# New_Project_ufcd_6024_2.net
KiCad netlist of a schematic drawn in EasyEDA Pro
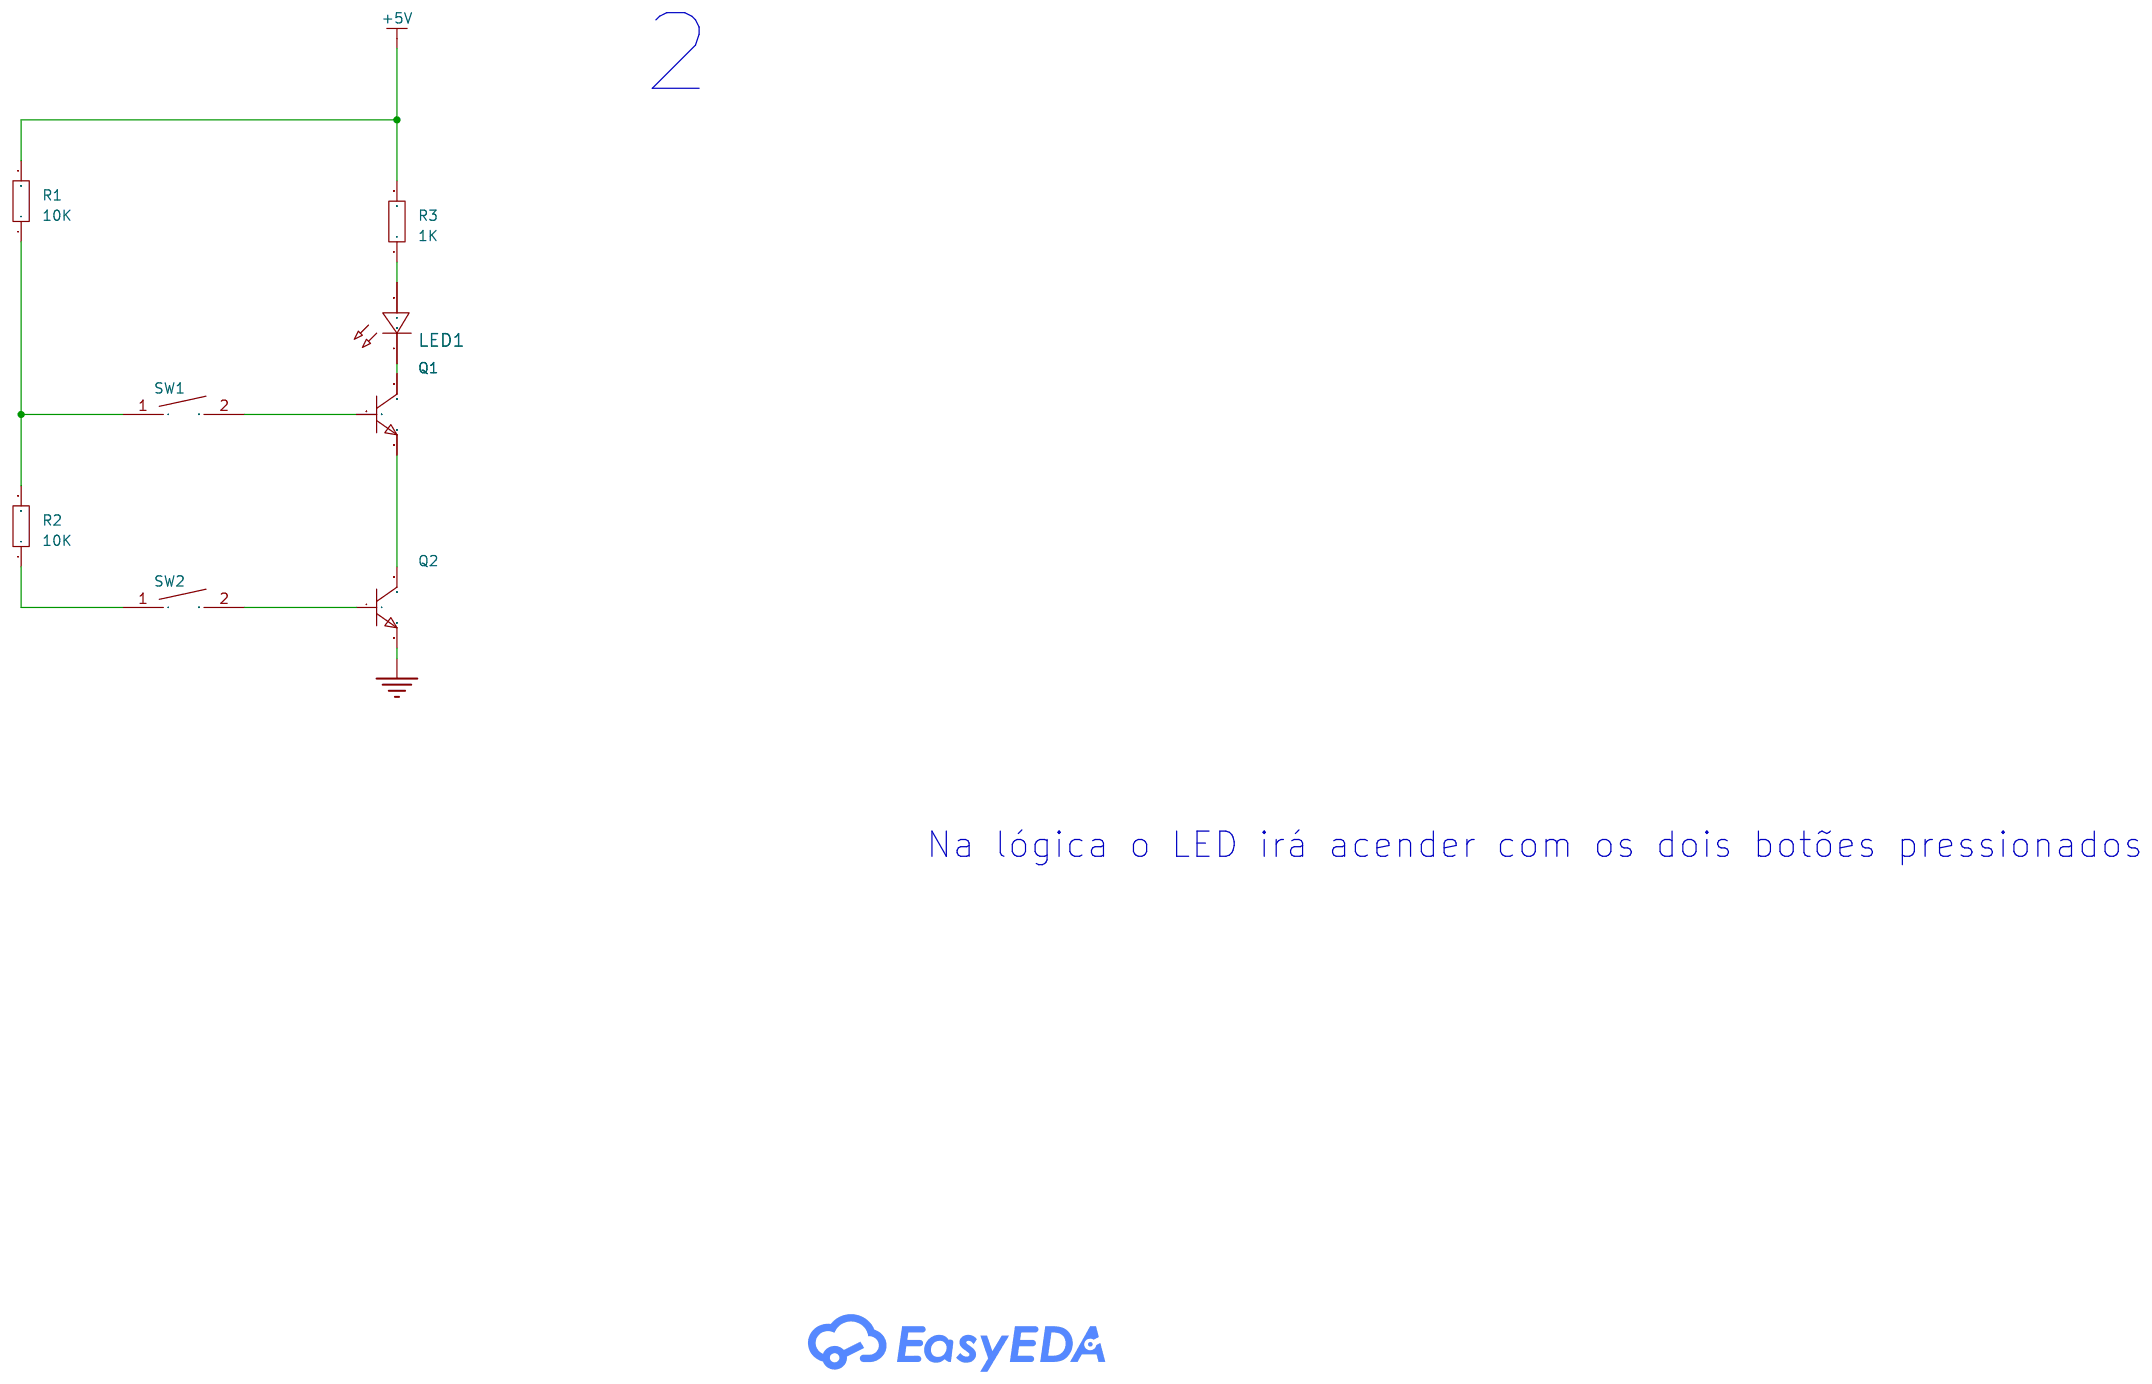
[diagram p0: schematic sheet]

(export (version "E")
  (design (tool "Eeschema 10.0.6"))
  (components
    (comp (ref "LED1")
      (value "~")
      (footprint "easyedapro:LED_0603")
      (libsource (lib "easyedapro") (part "LED_R"))
    )
    (comp (ref "Q1")
      (value "~")
      (footprint "easyedapro:S8050_SOT-23")
      (libsource (lib "easyedapro") (part "NPN"))
    )
    (comp (ref "Q2")
      (value "~")
      (footprint "easyedapro:S8050_SOT-23")
      (libsource (lib "easyedapro") (part "NPN"))
    )
    (comp (ref "R1") (value "10K") (footprint "easyedapro:R0603") (libsource (lib "easyedapro") (part "电阻")))
    (comp (ref "R2") (value "10K") (footprint "easyedapro:R0603") (libsource (lib "easyedapro") (part "电阻")))
    (comp (ref "R3") (value "1K") (footprint "easyedapro:R0603") (libsource (lib "easyedapro") (part "电阻")))
    (comp (ref "SW1")
      (value "~")
      (footprint "easyedapro:SW-TH_P7.00_SS11-RBDWQ-R20-R")
      (fields
        (field (name "Manufacturer Part") "SS11-RBDWQ-R20-R")
        (field (name "Manufacturer") "Legion(六钧)")
      )
      (libsource (lib "easyedapro") (part "SS11-RBDWQ-R20-R"))
    )
    (comp (ref "SW2")
      (value "~")
      (footprint "easyedapro:SW-TH_P7.00_SS11-RBDWQ-R20-R")
      (fields
        (field (name "Manufacturer Part") "SS11-RBDWQ-R20-R")
        (field (name "Manufacturer") "Legion(六钧)")
      )
      (libsource (lib "easyedapro") (part "SS11-RBDWQ-R20-R"))
    )
  )
  (nets
    (net (code "1") (name "+5V") (class "Default")
      (node (ref "R1") (pin "2") (pinfunction "2_2") (pintype "input"))
      (node (ref "R3") (pin "2") (pinfunction "2_2") (pintype "input"))
    )
    (net (code "2") (name "GND") (class "Default")
      (node (ref "Q2") (pin "2") (pinfunction "2_2") (pintype "unspecified"))
    )
    (net (code "3") (name "Net-(LED1-A)") (class "Default")
      (node (ref "LED1") (pin "2") (pinfunction "A_2") (pintype "input"))
      (node (ref "R3") (pin "1") (pinfunction "1_1") (pintype "input"))
    )
    (net (code "4") (name "Net-(LED1-C)") (class "Default")
      (node (ref "LED1") (pin "1") (pinfunction "C_1") (pintype "input"))
      (node (ref "Q1") (pin "3") (pinfunction "3_3") (pintype "unspecified"))
    )
    (net (code "5") (name "Net-(Q1-Pad1)") (class "Default")
      (node (ref "Q1") (pin "1") (pinfunction "1_1") (pintype "unspecified"))
      (node (ref "SW1") (pin "2") (pinfunction "2_2") (pintype "input"))
    )
    (net (code "6") (name "Net-(Q1-Pad2)") (class "Default")
      (node (ref "Q1") (pin "2") (pinfunction "2_2") (pintype "unspecified"))
      (node (ref "Q2") (pin "3") (pinfunction "3_3") (pintype "unspecified"))
    )
    (net (code "7") (name "Net-(Q2-Pad1)") (class "Default")
      (node (ref "Q2") (pin "1") (pinfunction "1_1") (pintype "unspecified"))
      (node (ref "SW2") (pin "2") (pinfunction "2_2") (pintype "input"))
    )
    (net (code "8") (name "Net-(R1-Pad1)") (class "Default")
      (node (ref "R1") (pin "1") (pinfunction "1_1") (pintype "input"))
      (node (ref "R2") (pin "2") (pinfunction "2_2") (pintype "input"))
      (node (ref "SW1") (pin "1") (pinfunction "1_1") (pintype "input"))
    )
    (net (code "9") (name "Net-(R2-Pad1)") (class "Default")
      (node (ref "R2") (pin "1") (pinfunction "1_1") (pintype "input"))
      (node (ref "SW2") (pin "1") (pinfunction "1_1") (pintype "input"))
    )
  )
)
